# nanoIO-v2.net
KiCad netlist of a schematic drawn in EAGLE
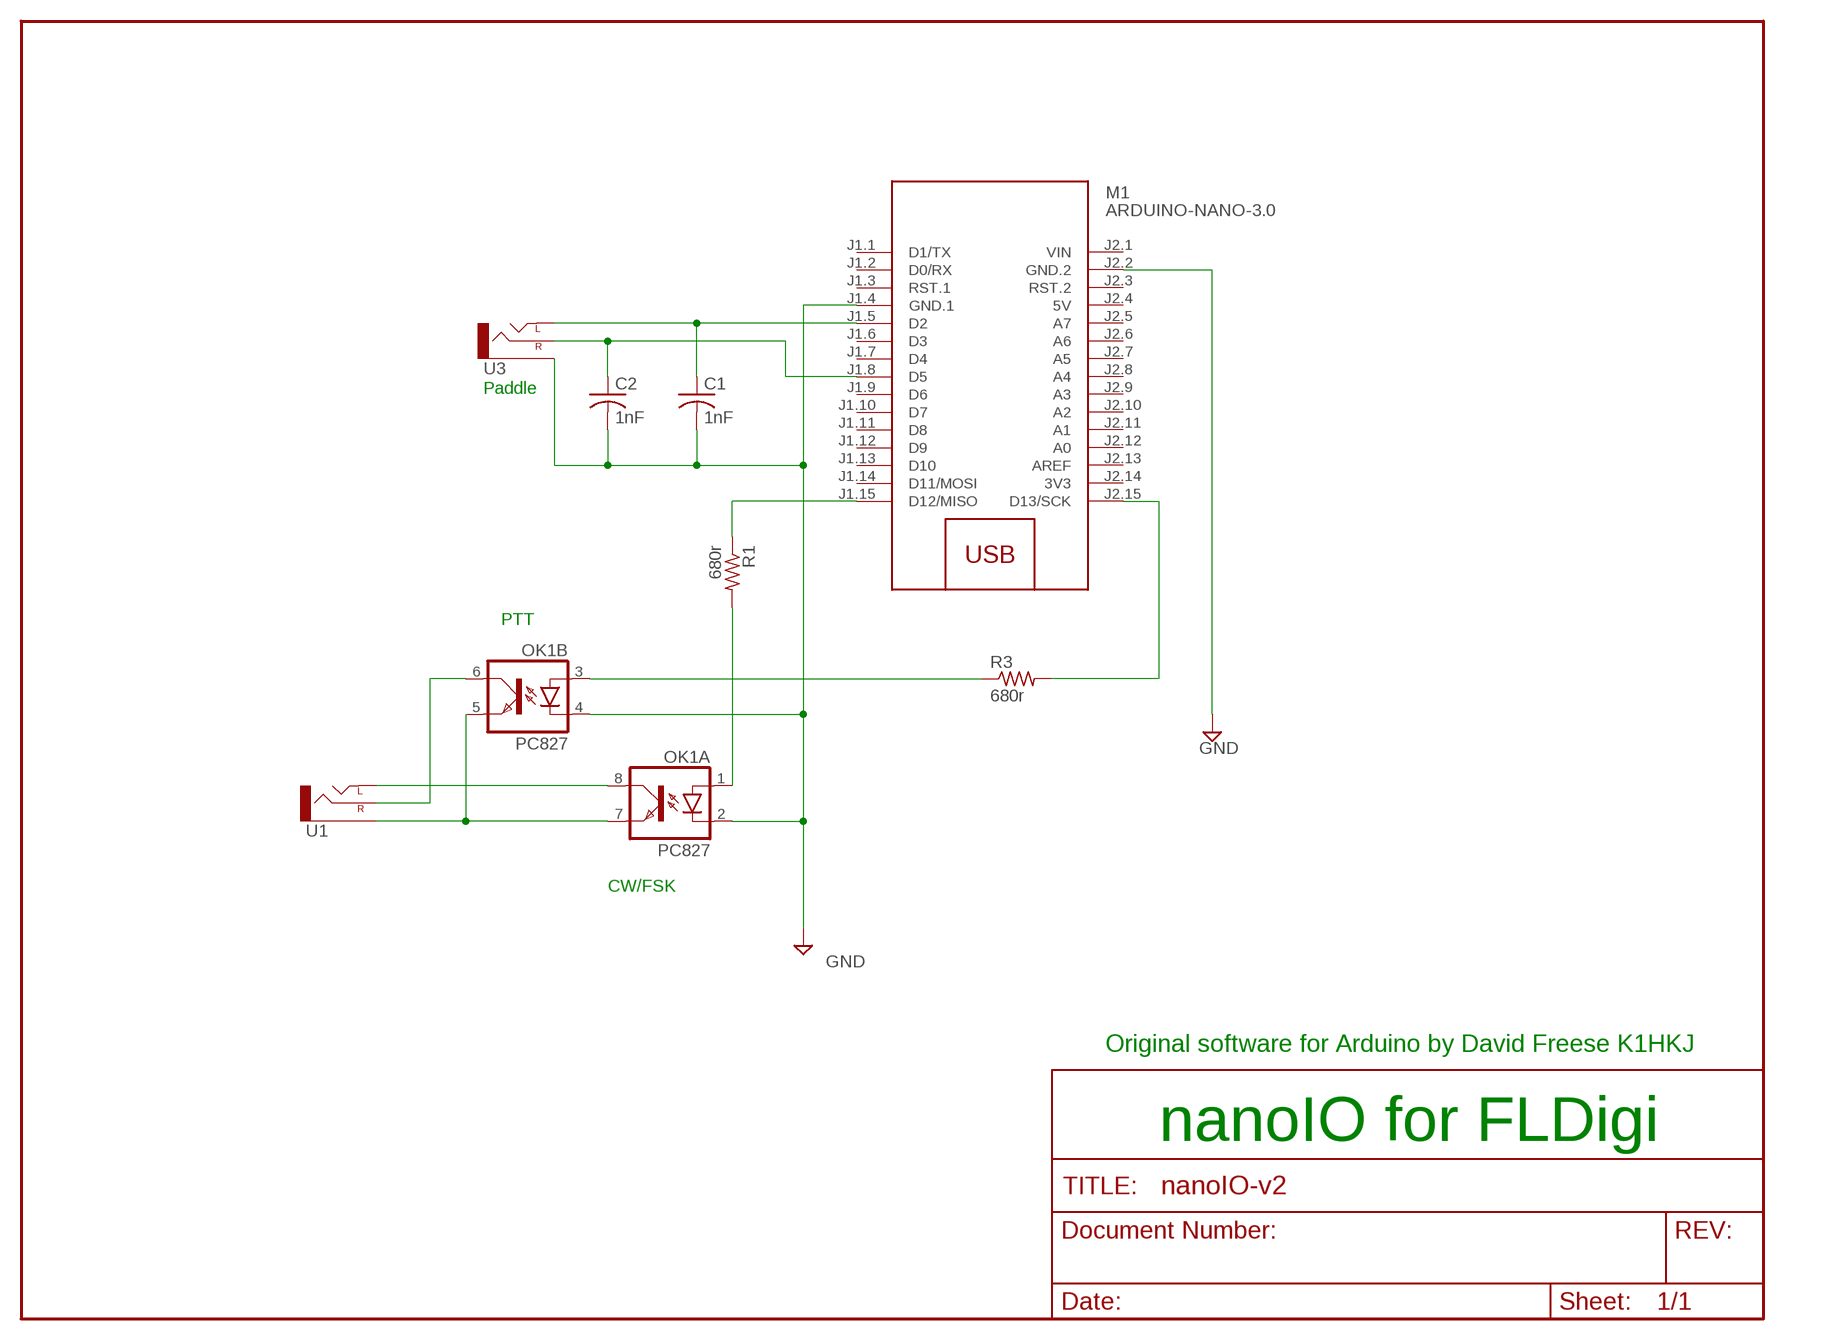
[diagram p0: schematic, sheet 1]

(export (version "E")
  (design (tool "Eeschema 10.0.6"))
  (components
    (comp (ref "C1")
      (value "1nF")
      (footprint "eagle-import:C025-025X050")
      (libsource (lib "eagle-import") (part "C-US025-025X050"))
    )
    (comp (ref "C2")
      (value "1nF")
      (footprint "eagle-import:C025-025X050")
      (libsource (lib "eagle-import") (part "C-US025-025X050"))
    )
    (comp (ref "M1")
      (value "ARDUINO-NANO-3.0")
      (footprint "eagle-import:ARDUINO-NANO-3.0")
      (libsource (lib "eagle-import") (part "ARDUINO-NANO-3.0"))
    )
    (comp (ref "OK1")
      (value "PC827")
      (footprint "eagle-import:DIL08")
      (libsource (lib "eagle-import") (part "PC827"))
    )
    (comp (ref "R1")
      (value "680r")
      (footprint "eagle-import:0204_7")
      (libsource (lib "eagle-import") (part "R-US_0204/7"))
    )
    (comp (ref "R3")
      (value "680r")
      (footprint "eagle-import:0204_7")
      (libsource (lib "eagle-import") (part "R-US_0204/7"))
    )
    (comp (ref "U1")
      (value "AUDIO-JACKPTH")
      (footprint "eagle-import:AUDIO-JACK")
      (libsource (lib "eagle-import") (part "AUDIO-JACKPTH"))
    )
    (comp (ref "U3")
      (value "AUDIO-JACKPTH")
      (footprint "eagle-import:AUDIO-JACK")
      (libsource (lib "eagle-import") (part "AUDIO-JACKPTH"))
    )
  )
  (nets
    (net (code "1") (name "/3V3") (class "Default")
      (node (ref "M1") (pin "J2.14") (pinfunction "3V3_J2.14") (pintype "power_in"))
    )
    (net (code "2") (name "/5V") (class "Default")
      (node (ref "M1") (pin "J2.4") (pinfunction "5V_J2.4") (pintype "power_in"))
    )
    (net (code "3") (name "/VIN") (class "Default")
      (node (ref "M1") (pin "J2.1") (pinfunction "VIN_J2.1") (pintype "power_in"))
    )
    (net (code "4") (name "GND") (class "Default")
      (node (ref "C1") (pin "2") (pinfunction "2_2") (pintype "passive"))
      (node (ref "C2") (pin "2") (pinfunction "2_2") (pintype "passive"))
      (node (ref "M1") (pin "J1.4") (pinfunction "GND.1_J1.4") (pintype "power_in"))
      (node (ref "M1") (pin "J2.2") (pinfunction "GND.2_J2.2") (pintype "power_in"))
      (node (ref "OK1") (pin "2") (pinfunction "C_2") (pintype "passive"))
      (node (ref "OK1") (pin "4") (pinfunction "C_4") (pintype "passive"))
      (node (ref "U3") (pin "SLEEVE") (pinfunction "SLEEVE_SLEEVE") (pintype "bidirectional"))
    )
    (net (code "5") (name "Net-(M1-D2)") (class "Default")
      (node (ref "C1") (pin "1") (pinfunction "1_1") (pintype "passive"))
      (node (ref "M1") (pin "J1.5") (pinfunction "D2_J1.5") (pintype "bidirectional"))
      (node (ref "U3") (pin "TIP") (pinfunction "LEFT_TIP") (pintype "bidirectional"))
    )
    (net (code "6") (name "Net-(M1-D5)") (class "Default")
      (node (ref "C2") (pin "1") (pinfunction "1_1") (pintype "passive"))
      (node (ref "M1") (pin "J1.8") (pinfunction "D5_J1.8") (pintype "bidirectional"))
      (node (ref "U3") (pin "RING") (pinfunction "RIGHT_RING") (pintype "bidirectional"))
    )
    (net (code "7") (name "Net-(M1-D12{slash}MISO)") (class "Default")
      (node (ref "M1") (pin "J1.15") (pinfunction "D12/MISO_J1.15") (pintype "bidirectional"))
      (node (ref "R1") (pin "1") (pinfunction "1_1") (pintype "passive"))
    )
    (net (code "8") (name "Net-(M1-D13{slash}SCK)") (class "Default")
      (node (ref "M1") (pin "J2.15") (pinfunction "D13/SCK_J2.15") (pintype "bidirectional"))
      (node (ref "R3") (pin "2") (pinfunction "2_2") (pintype "passive"))
    )
    (net (code "9") (name "Net-(OK1A-A)") (class "Default")
      (node (ref "OK1") (pin "1") (pinfunction "A_1") (pintype "passive"))
      (node (ref "R1") (pin "2") (pinfunction "2_2") (pintype "passive"))
    )
    (net (code "10") (name "Net-(OK1A-COL)") (class "Default")
      (node (ref "OK1") (pin "8") (pinfunction "COL_8") (pintype "passive"))
      (node (ref "U1") (pin "TIP") (pinfunction "LEFT_TIP") (pintype "bidirectional"))
    )
    (net (code "11") (name "Net-(OK1A-EMIT)") (class "Default")
      (node (ref "OK1") (pin "5") (pinfunction "EMIT_5") (pintype "passive"))
      (node (ref "OK1") (pin "7") (pinfunction "EMIT_7") (pintype "passive"))
      (node (ref "U1") (pin "SLEEVE") (pinfunction "SLEEVE_SLEEVE") (pintype "bidirectional"))
    )
    (net (code "12") (name "Net-(OK1B-A)") (class "Default")
      (node (ref "OK1") (pin "3") (pinfunction "A_3") (pintype "passive"))
      (node (ref "R3") (pin "1") (pinfunction "1_1") (pintype "passive"))
    )
    (net (code "13") (name "Net-(OK1B-COL)") (class "Default")
      (node (ref "OK1") (pin "6") (pinfunction "COL_6") (pintype "passive"))
      (node (ref "U1") (pin "RING") (pinfunction "RIGHT_RING") (pintype "bidirectional"))
    )
    (net (code "14") (name "unconnected-(M1-A0-PadJ2.12)") (class "Default")
      (node (ref "M1") (pin "J2.12") (pinfunction "A0_J2.12") (pintype "bidirectional"))
    )
    (net (code "15") (name "unconnected-(M1-A1-PadJ2.11)") (class "Default")
      (node (ref "M1") (pin "J2.11") (pinfunction "A1_J2.11") (pintype "bidirectional"))
    )
    (net (code "16") (name "unconnected-(M1-A2-PadJ2.10)") (class "Default")
      (node (ref "M1") (pin "J2.10") (pinfunction "A2_J2.10") (pintype "bidirectional"))
    )
    (net (code "17") (name "unconnected-(M1-A3-PadJ2.9)") (class "Default")
      (node (ref "M1") (pin "J2.9") (pinfunction "A3_J2.9") (pintype "bidirectional"))
    )
    (net (code "18") (name "unconnected-(M1-A4-PadJ2.8)") (class "Default")
      (node (ref "M1") (pin "J2.8") (pinfunction "A4_J2.8") (pintype "bidirectional"))
    )
    (net (code "19") (name "unconnected-(M1-A5-PadJ2.7)") (class "Default")
      (node (ref "M1") (pin "J2.7") (pinfunction "A5_J2.7") (pintype "bidirectional"))
    )
    (net (code "20") (name "unconnected-(M1-A6-PadJ2.6)") (class "Default")
      (node (ref "M1") (pin "J2.6") (pinfunction "A6_J2.6") (pintype "bidirectional"))
    )
    (net (code "21") (name "unconnected-(M1-A7-PadJ2.5)") (class "Default")
      (node (ref "M1") (pin "J2.5") (pinfunction "A7_J2.5") (pintype "bidirectional"))
    )
    (net (code "22") (name "unconnected-(M1-AREF-PadJ2.13)") (class "Default")
      (node (ref "M1") (pin "J2.13") (pinfunction "AREF_J2.13") (pintype "bidirectional"))
    )
    (net (code "23") (name "unconnected-(M1-D0{slash}RX-PadJ1.2)") (class "Default")
      (node (ref "M1") (pin "J1.2") (pinfunction "D0/RX_J1.2") (pintype "bidirectional"))
    )
    (net (code "24") (name "unconnected-(M1-D1{slash}TX-PadJ1.1)") (class "Default")
      (node (ref "M1") (pin "J1.1") (pinfunction "D1/TX_J1.1") (pintype "bidirectional"))
    )
    (net (code "25") (name "unconnected-(M1-D3-PadJ1.6)") (class "Default")
      (node (ref "M1") (pin "J1.6") (pinfunction "D3_J1.6") (pintype "bidirectional"))
    )
    (net (code "26") (name "unconnected-(M1-D4-PadJ1.7)") (class "Default")
      (node (ref "M1") (pin "J1.7") (pinfunction "D4_J1.7") (pintype "bidirectional"))
    )
    (net (code "27") (name "unconnected-(M1-D6-PadJ1.9)") (class "Default")
      (node (ref "M1") (pin "J1.9") (pinfunction "D6_J1.9") (pintype "bidirectional"))
    )
    (net (code "28") (name "unconnected-(M1-D7-PadJ1.10)") (class "Default")
      (node (ref "M1") (pin "J1.10") (pinfunction "D7_J1.10") (pintype "bidirectional"))
    )
    (net (code "29") (name "unconnected-(M1-D8-PadJ1.11)") (class "Default")
      (node (ref "M1") (pin "J1.11") (pinfunction "D8_J1.11") (pintype "bidirectional"))
    )
    (net (code "30") (name "unconnected-(M1-D9-PadJ1.12)") (class "Default")
      (node (ref "M1") (pin "J1.12") (pinfunction "D9_J1.12") (pintype "bidirectional"))
    )
    (net (code "31") (name "unconnected-(M1-D10-PadJ1.13)") (class "Default")
      (node (ref "M1") (pin "J1.13") (pinfunction "D10_J1.13") (pintype "bidirectional"))
    )
    (net (code "32") (name "unconnected-(M1-D11{slash}MOSI-PadJ1.14)") (class "Default")
      (node (ref "M1") (pin "J1.14") (pinfunction "D11/MOSI_J1.14") (pintype "bidirectional"))
    )
    (net (code "33") (name "unconnected-(M1-RST.1-PadJ1.3)") (class "Default")
      (node (ref "M1") (pin "J1.3") (pinfunction "RST.1_J1.3") (pintype "bidirectional"))
    )
    (net (code "34") (name "unconnected-(M1-RST.2-PadJ2.3)") (class "Default")
      (node (ref "M1") (pin "J2.3") (pinfunction "RST.2_J2.3") (pintype "bidirectional"))
    )
  )
)
